# Wifi_Schemati.net
KiCad netlist of a schematic drawn in EAGLE
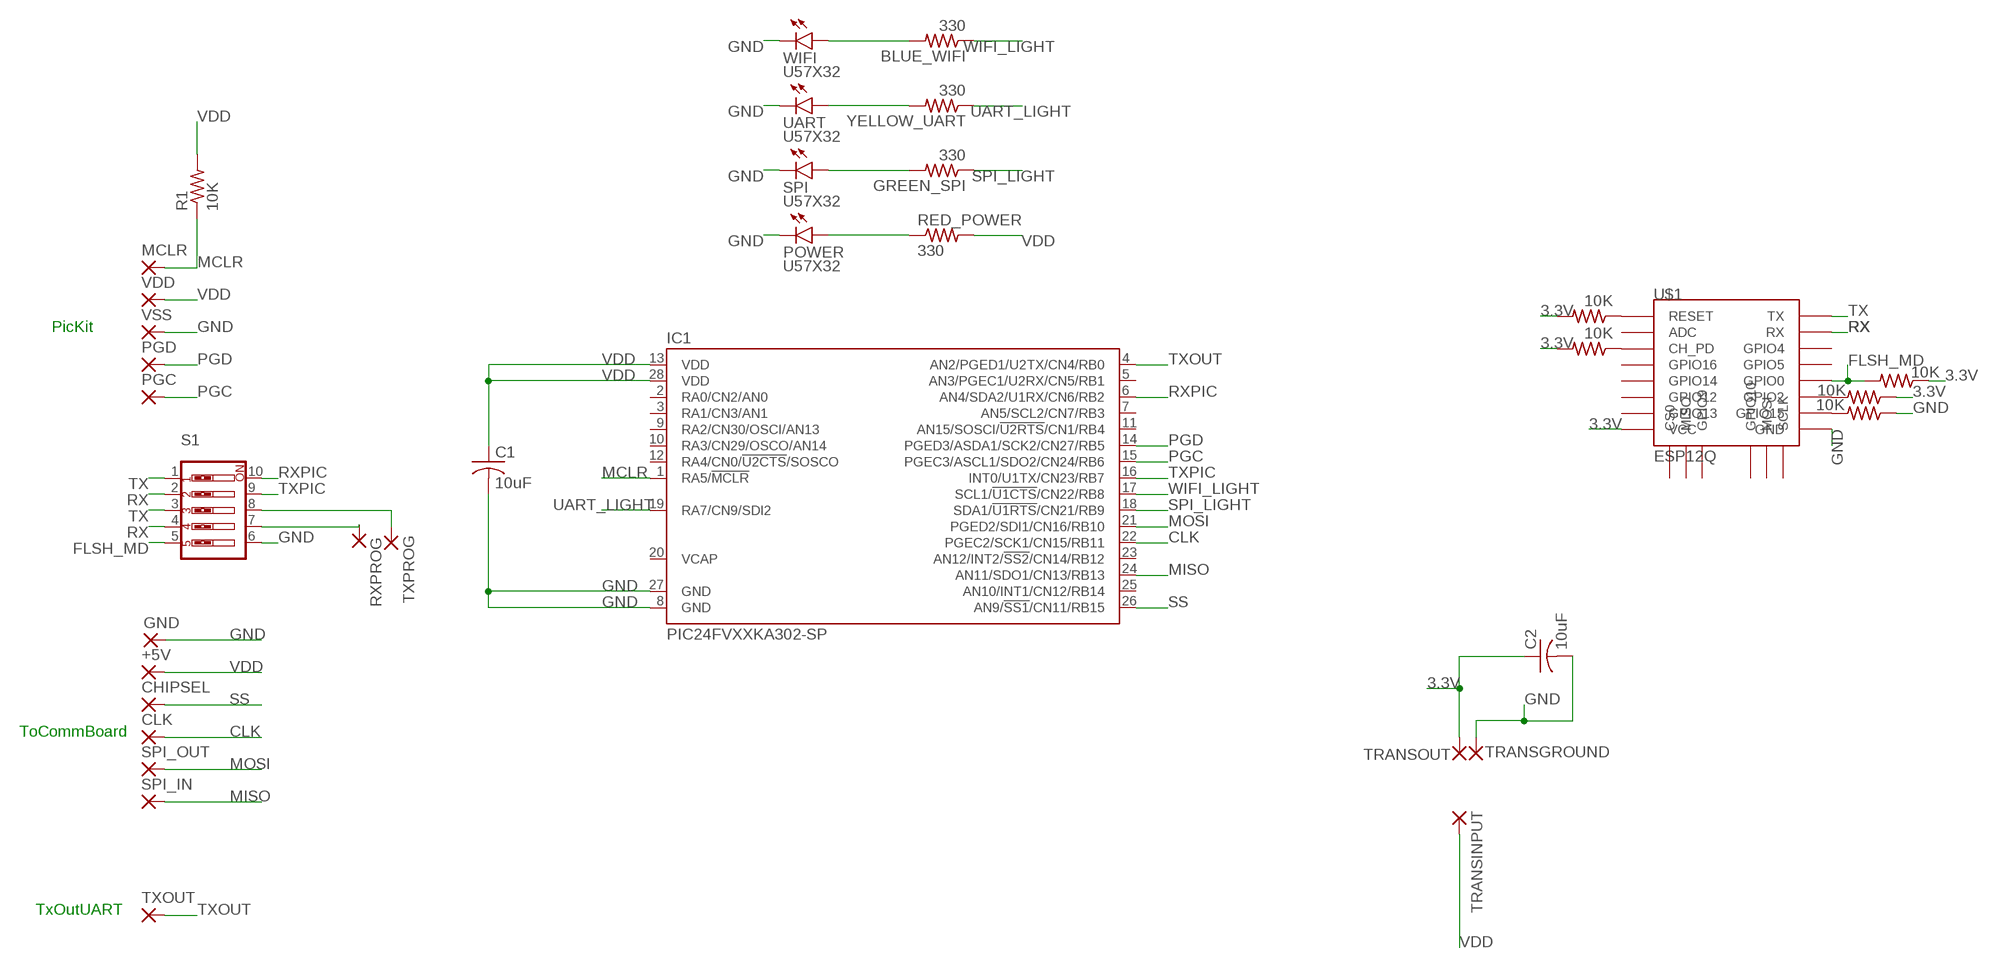
[diagram p0: schematic, sheet 1]

(export (version "E")
  (design (tool "Eeschema 10.0.6"))
  (components
    (comp (ref "+5V")
      (value "1,6/0,8")
      (footprint "eagle-import:1,6_0,8")
      (libsource (lib "eagle-import") (part "1,6/0,8"))
    )
    (comp (ref "BLUE_WIFI")
      (value "330")
      (footprint "eagle-import:0207_7")
      (libsource (lib "eagle-import") (part "R-US_0207/7"))
    )
    (comp (ref "C1")
      (value "10uF")
      (footprint "eagle-import:C025-025X050")
      (libsource (lib "eagle-import") (part "C-US025-025X050"))
    )
    (comp (ref "C2")
      (value "10uF")
      (footprint "eagle-import:C025-025X050")
      (libsource (lib "eagle-import") (part "C-US025-025X050"))
    )
    (comp (ref "CHIPSEL")
      (value "1,6/0,8")
      (footprint "eagle-import:1,6_0,8")
      (libsource (lib "eagle-import") (part "1,6/0,8"))
    )
    (comp (ref "CLK")
      (value "1,6/0,8")
      (footprint "eagle-import:1,6_0,8")
      (libsource (lib "eagle-import") (part "1,6/0,8"))
    )
    (comp (ref "GND")
      (value "1,6/0,8")
      (footprint "eagle-import:1,6_0,8")
      (libsource (lib "eagle-import") (part "1,6/0,8"))
    )
    (comp (ref "GREEN_SPI")
      (value "330")
      (footprint "eagle-import:0207_7")
      (libsource (lib "eagle-import") (part "R-US_0207/7"))
    )
    (comp (ref "IC1")
      (value "PIC24FVXXKA302-SP")
      (footprint "eagle-import:DIL28-3")
      (libsource (lib "eagle-import") (part "PIC24FVXXKA302-SP"))
    )
    (comp (ref "MCLR")
      (value "1,6/0,8")
      (footprint "eagle-import:1,6_0,8")
      (libsource (lib "eagle-import") (part "1,6/0,8"))
    )
    (comp (ref "PGC")
      (value "1,6/0,8")
      (footprint "eagle-import:1,6_0,8")
      (libsource (lib "eagle-import") (part "1,6/0,8"))
    )
    (comp (ref "PGD")
      (value "1,6/0,8")
      (footprint "eagle-import:1,6_0,8")
      (libsource (lib "eagle-import") (part "1,6/0,8"))
    )
    (comp (ref "POWER")
      (value "U57X32")
      (footprint "eagle-import:U57X32")
      (libsource (lib "eagle-import") (part "U57X32"))
    )
    (comp (ref "R1")
      (value "10K")
      (footprint "eagle-import:0207_7")
      (libsource (lib "eagle-import") (part "R-US_0207/7"))
    )
    (comp (ref "R2")
      (value "10K")
      (footprint "eagle-import:0207_7")
      (libsource (lib "eagle-import") (part "R-US_0207/7"))
    )
    (comp (ref "R3")
      (value "10K")
      (footprint "eagle-import:0207_7")
      (libsource (lib "eagle-import") (part "R-US_0207/7"))
    )
    (comp (ref "R4")
      (value "10K")
      (footprint "eagle-import:0207_7")
      (libsource (lib "eagle-import") (part "R-US_0207/7"))
    )
    (comp (ref "R5")
      (value "10K")
      (footprint "eagle-import:0207_7")
      (libsource (lib "eagle-import") (part "R-US_0207/7"))
    )
    (comp (ref "R6")
      (value "10K")
      (footprint "eagle-import:0207_7")
      (libsource (lib "eagle-import") (part "R-US_0207/7"))
    )
    (comp (ref "RED_POWER")
      (value "330")
      (footprint "eagle-import:0207_7")
      (libsource (lib "eagle-import") (part "R-US_0207/7"))
    )
    (comp (ref "RXPROG")
      (value "1,6/0,8")
      (footprint "eagle-import:1,6_0,8")
      (libsource (lib "eagle-import") (part "1,6/0,8"))
    )
    (comp (ref "S1")
      (value "SW_DIP-5")
      (footprint "eagle-import:EDG-05")
      (libsource (lib "eagle-import") (part "SW_DIP-5"))
    )
    (comp (ref "SPI")
      (value "U57X32")
      (footprint "eagle-import:U57X32")
      (libsource (lib "eagle-import") (part "U57X32"))
    )
    (comp (ref "SPI_IN")
      (value "1,6/0,8")
      (footprint "eagle-import:1,6_0,8")
      (libsource (lib "eagle-import") (part "1,6/0,8"))
    )
    (comp (ref "SPI_OUT")
      (value "1,6/0,8")
      (footprint "eagle-import:1,6_0,8")
      (libsource (lib "eagle-import") (part "1,6/0,8"))
    )
    (comp (ref "TRANSGROUND")
      (value "1,6/0,8")
      (footprint "eagle-import:1,6_0,8")
      (libsource (lib "eagle-import") (part "1,6/0,8"))
    )
    (comp (ref "TRANSINPUT")
      (value "1,6/0,8")
      (footprint "eagle-import:1,6_0,8")
      (libsource (lib "eagle-import") (part "1,6/0,8"))
    )
    (comp (ref "TRANSOUT")
      (value "1,6/0,8")
      (footprint "eagle-import:1,6_0,8")
      (libsource (lib "eagle-import") (part "1,6/0,8"))
    )
    (comp (ref "TXOUT")
      (value "1,6/0,8")
      (footprint "eagle-import:1,6_0,8")
      (libsource (lib "eagle-import") (part "1,6/0,8"))
    )
    (comp (ref "TXPROG")
      (value "1,6/0,8")
      (footprint "eagle-import:1,6_0,8")
      (libsource (lib "eagle-import") (part "1,6/0,8"))
    )
    (comp (ref "U$1")
      (value "ESP12Q")
      (footprint "eagle-import:ESP12Q")
      (fields (field (name "SPICEPREFIX") "X"))
      (libsource (lib "eagle-import") (part "ESP12Q"))
    )
    (comp (ref "UART")
      (value "U57X32")
      (footprint "eagle-import:U57X32")
      (libsource (lib "eagle-import") (part "U57X32"))
    )
    (comp (ref "VDD")
      (value "1,6/0,8")
      (footprint "eagle-import:1,6_0,8")
      (libsource (lib "eagle-import") (part "1,6/0,8"))
    )
    (comp (ref "VSS")
      (value "1,6/0,8")
      (footprint "eagle-import:1,6_0,8")
      (libsource (lib "eagle-import") (part "1,6/0,8"))
    )
    (comp (ref "WIFI")
      (value "U57X32")
      (footprint "eagle-import:U57X32")
      (libsource (lib "eagle-import") (part "U57X32"))
    )
    (comp (ref "YELLOW_UART")
      (value "330")
      (footprint "eagle-import:0207_7")
      (libsource (lib "eagle-import") (part "R-US_0207/7"))
    )
  )
  (nets
    (net (code "1") (name "/3.3V") (class "Default")
      (node (ref "C2") (pin "1") (pinfunction "1_1") (pintype "passive"))
      (node (ref "R3") (pin "1") (pinfunction "1_1") (pintype "passive"))
      (node (ref "R4") (pin "1") (pinfunction "1_1") (pintype "passive"))
      (node (ref "R5") (pin "2") (pinfunction "2_2") (pintype "passive"))
      (node (ref "R6") (pin "2") (pinfunction "2_2") (pintype "passive"))
      (node (ref "TRANSOUT") (pin "1") (pinfunction "P_1") (pintype "passive"))
      (node (ref "U$1") (pin "VCC") (pinfunction "VCC_VCC") (pintype "bidirectional"))
    )
    (net (code "2") (name "/CLK") (class "Default")
      (node (ref "CLK") (pin "1") (pinfunction "P_1") (pintype "passive"))
      (node (ref "IC1") (pin "22") (pinfunction "PGEC2/SCK1/CN15/RB11_22") (pintype "bidirectional"))
    )
    (net (code "3") (name "/FLSH_MD") (class "Default")
      (node (ref "R4") (pin "2") (pinfunction "2_2") (pintype "passive"))
      (node (ref "S1") (pin "5") (pinfunction "5_5") (pintype "passive"))
      (node (ref "U$1") (pin "GPIO0") (pinfunction "GPIO0_GPIO0") (pintype "bidirectional"))
    )
    (net (code "4") (name "/GND") (class "Default")
      (node (ref "C1") (pin "2") (pinfunction "2_2") (pintype "passive"))
      (node (ref "C2") (pin "2") (pinfunction "2_2") (pintype "passive"))
      (node (ref "GND") (pin "1") (pinfunction "P_1") (pintype "passive"))
      (node (ref "IC1") (pin "27") (pinfunction "GND_27") (pintype "power_in"))
      (node (ref "IC1") (pin "8") (pinfunction "GND_8") (pintype "power_in"))
      (node (ref "POWER") (pin "K") (pinfunction "C_K") (pintype "passive"))
      (node (ref "R2") (pin "1") (pinfunction "1_1") (pintype "passive"))
      (node (ref "S1") (pin "6") (pinfunction "6_6") (pintype "passive"))
      (node (ref "SPI") (pin "K") (pinfunction "C_K") (pintype "passive"))
      (node (ref "TRANSGROUND") (pin "1") (pinfunction "P_1") (pintype "passive"))
      (node (ref "U$1") (pin "GND") (pinfunction "GND_GND") (pintype "bidirectional"))
      (node (ref "UART") (pin "K") (pinfunction "C_K") (pintype "passive"))
      (node (ref "VSS") (pin "1") (pinfunction "P_1") (pintype "passive"))
      (node (ref "WIFI") (pin "K") (pinfunction "C_K") (pintype "passive"))
    )
    (net (code "5") (name "/MCLR") (class "Default")
      (node (ref "IC1") (pin "1") (pinfunction "RA5/~{MCLR}_1") (pintype "bidirectional"))
      (node (ref "MCLR") (pin "1") (pinfunction "P_1") (pintype "passive"))
      (node (ref "R1") (pin "1") (pinfunction "1_1") (pintype "passive"))
    )
    (net (code "6") (name "/MISO") (class "Default")
      (node (ref "IC1") (pin "24") (pinfunction "AN11/SDO1/CN13/RB13_24") (pintype "bidirectional"))
      (node (ref "SPI_IN") (pin "1") (pinfunction "P_1") (pintype "passive"))
    )
    (net (code "7") (name "/MOSI") (class "Default")
      (node (ref "IC1") (pin "21") (pinfunction "PGED2/SDI1/CN16/RB10_21") (pintype "bidirectional"))
      (node (ref "SPI_OUT") (pin "1") (pinfunction "P_1") (pintype "passive"))
    )
    (net (code "8") (name "/PGC") (class "Default")
      (node (ref "IC1") (pin "15") (pinfunction "PGEC3/ASCL1/SDO2/CN24/RB6_15") (pintype "bidirectional"))
      (node (ref "PGC") (pin "1") (pinfunction "P_1") (pintype "passive"))
    )
    (net (code "9") (name "/PGD") (class "Default")
      (node (ref "IC1") (pin "14") (pinfunction "PGED3/ASDA1/SCK2/CN27/RB5_14") (pintype "bidirectional"))
      (node (ref "PGD") (pin "1") (pinfunction "P_1") (pintype "passive"))
    )
    (net (code "10") (name "/RX") (class "Default")
      (node (ref "S1") (pin "2") (pinfunction "2_2") (pintype "passive"))
      (node (ref "S1") (pin "4") (pinfunction "4_4") (pintype "passive"))
      (node (ref "U$1") (pin "RX") (pinfunction "RX_RX") (pintype "bidirectional"))
    )
    (net (code "11") (name "/RXPIC") (class "Default")
      (node (ref "IC1") (pin "6") (pinfunction "AN4/SDA2/U1RX/CN6/RB2_6") (pintype "bidirectional"))
      (node (ref "S1") (pin "10") (pinfunction "10_10") (pintype "passive"))
    )
    (net (code "12") (name "/SPI_LIGHT") (class "Default")
      (node (ref "GREEN_SPI") (pin "1") (pinfunction "1_1") (pintype "passive"))
      (node (ref "IC1") (pin "18") (pinfunction "SDA1/~{U1RTS}/CN21/RB9_18") (pintype "bidirectional"))
    )
    (net (code "13") (name "/SS") (class "Default")
      (node (ref "CHIPSEL") (pin "1") (pinfunction "P_1") (pintype "passive"))
      (node (ref "IC1") (pin "26") (pinfunction "AN9/~{SS1}/CN11/RB15_26") (pintype "bidirectional"))
    )
    (net (code "14") (name "/TX") (class "Default")
      (node (ref "S1") (pin "1") (pinfunction "1_1") (pintype "passive"))
      (node (ref "S1") (pin "3") (pinfunction "3_3") (pintype "passive"))
      (node (ref "U$1") (pin "TX") (pinfunction "TX_TX") (pintype "bidirectional"))
    )
    (net (code "15") (name "/TXOUT") (class "Default")
      (node (ref "IC1") (pin "4") (pinfunction "AN2/PGED1/U2TX/CN4/RB0_4") (pintype "bidirectional"))
      (node (ref "TXOUT") (pin "1") (pinfunction "P_1") (pintype "passive"))
    )
    (net (code "16") (name "/TXPIC") (class "Default")
      (node (ref "IC1") (pin "16") (pinfunction "INT0/U1TX/CN23/RB7_16") (pintype "bidirectional"))
      (node (ref "S1") (pin "9") (pinfunction "9_9") (pintype "passive"))
    )
    (net (code "17") (name "/UART_LIGHT") (class "Default")
      (node (ref "IC1") (pin "19") (pinfunction "RA7/CN9/SDI2_19") (pintype "bidirectional"))
      (node (ref "YELLOW_UART") (pin "1") (pinfunction "1_1") (pintype "passive"))
    )
    (net (code "18") (name "/VDD") (class "Default")
      (node (ref "+5V") (pin "1") (pinfunction "P_1") (pintype "passive"))
      (node (ref "C1") (pin "1") (pinfunction "1_1") (pintype "passive"))
      (node (ref "IC1") (pin "13") (pinfunction "VDD_13") (pintype "power_in"))
      (node (ref "IC1") (pin "28") (pinfunction "VDD_28") (pintype "power_in"))
      (node (ref "R1") (pin "2") (pinfunction "2_2") (pintype "passive"))
      (node (ref "RED_POWER") (pin "2") (pinfunction "2_2") (pintype "passive"))
      (node (ref "TRANSINPUT") (pin "1") (pinfunction "P_1") (pintype "passive"))
      (node (ref "VDD") (pin "1") (pinfunction "P_1") (pintype "passive"))
    )
    (net (code "19") (name "/WIFI_LIGHT") (class "Default")
      (node (ref "BLUE_WIFI") (pin "1") (pinfunction "1_1") (pintype "passive"))
      (node (ref "IC1") (pin "17") (pinfunction "SCL1/~{U1CTS}/CN22/RB8_17") (pintype "bidirectional"))
    )
    (net (code "20") (name "Net-(BLUE_WIFI-Pad2)") (class "Default")
      (node (ref "BLUE_WIFI") (pin "2") (pinfunction "2_2") (pintype "passive"))
      (node (ref "WIFI") (pin "A") (pinfunction "A_A") (pintype "passive"))
    )
    (net (code "21") (name "Net-(GREEN_SPI-Pad2)") (class "Default")
      (node (ref "GREEN_SPI") (pin "2") (pinfunction "2_2") (pintype "passive"))
      (node (ref "SPI") (pin "A") (pinfunction "A_A") (pintype "passive"))
    )
    (net (code "22") (name "Net-(POWER-PadA)") (class "Default")
      (node (ref "POWER") (pin "A") (pinfunction "A_A") (pintype "passive"))
      (node (ref "RED_POWER") (pin "1") (pinfunction "1_1") (pintype "passive"))
    )
    (net (code "23") (name "Net-(R2-Pad2)") (class "Default")
      (node (ref "R2") (pin "2") (pinfunction "2_2") (pintype "passive"))
      (node (ref "U$1") (pin "GPIO15") (pinfunction "GPIO15_GPIO15") (pintype "bidirectional"))
    )
    (net (code "24") (name "Net-(R3-Pad2)") (class "Default")
      (node (ref "R3") (pin "2") (pinfunction "2_2") (pintype "passive"))
      (node (ref "U$1") (pin "GPIO2") (pinfunction "GPIO2_GPIO2") (pintype "bidirectional"))
    )
    (net (code "25") (name "Net-(R5-Pad1)") (class "Default")
      (node (ref "R5") (pin "1") (pinfunction "1_1") (pintype "passive"))
      (node (ref "U$1") (pin "RESET") (pinfunction "RESET_RESET") (pintype "bidirectional"))
    )
    (net (code "26") (name "Net-(R6-Pad1)") (class "Default")
      (node (ref "R6") (pin "1") (pinfunction "1_1") (pintype "passive"))
      (node (ref "U$1") (pin "CH_PD") (pinfunction "CH_PD_CH_PD") (pintype "bidirectional"))
    )
    (net (code "27") (name "Net-(RXPROG-P)") (class "Default")
      (node (ref "RXPROG") (pin "1") (pinfunction "P_1") (pintype "passive"))
      (node (ref "S1") (pin "7") (pinfunction "7_7") (pintype "passive"))
    )
    (net (code "28") (name "Net-(TXPROG-P)") (class "Default")
      (node (ref "S1") (pin "8") (pinfunction "8_8") (pintype "passive"))
      (node (ref "TXPROG") (pin "1") (pinfunction "P_1") (pintype "passive"))
    )
    (net (code "29") (name "Net-(UART-PadA)") (class "Default")
      (node (ref "UART") (pin "A") (pinfunction "A_A") (pintype "passive"))
      (node (ref "YELLOW_UART") (pin "2") (pinfunction "2_2") (pintype "passive"))
    )
    (net (code "30") (name "unconnected-(IC1-AN3{slash}PGEC1{slash}U2RX{slash}CN5{slash}RB1-Pad5)") (class "Default")
      (node (ref "IC1") (pin "5") (pinfunction "AN3/PGEC1/U2RX/CN5/RB1_5") (pintype "bidirectional"))
    )
    (net (code "31") (name "unconnected-(IC1-AN5{slash}SCL2{slash}CN7{slash}RB3-Pad7)") (class "Default")
      (node (ref "IC1") (pin "7") (pinfunction "AN5/SCL2/CN7/RB3_7") (pintype "bidirectional"))
    )
    (net (code "32") (name "unconnected-(IC1-AN10{slash}INT1{slash}CN12{slash}RB14-Pad25)") (class "Default")
      (node (ref "IC1") (pin "25") (pinfunction "AN10/INT1/CN12/RB14_25") (pintype "bidirectional"))
    )
    (net (code "33") (name "unconnected-(IC1-AN12{slash}INT2{slash}~{SS2}{slash}CN14{slash}RB12-Pad23)") (class "Default")
      (node (ref "IC1") (pin "23") (pinfunction "AN12/INT2/~{SS2}/CN14/RB12_23") (pintype "bidirectional"))
    )
    (net (code "34") (name "unconnected-(IC1-AN15{slash}SOSCI{slash}~{U2RTS}{slash}CN1{slash}RB4-Pad11)") (class "Default")
      (node (ref "IC1") (pin "11") (pinfunction "AN15/SOSCI/~{U2RTS}/CN1/RB4_11") (pintype "bidirectional"))
    )
    (net (code "35") (name "unconnected-(IC1-RA0{slash}CN2{slash}AN0-Pad2)") (class "Default")
      (node (ref "IC1") (pin "2") (pinfunction "RA0/CN2/AN0_2") (pintype "bidirectional"))
    )
    (net (code "36") (name "unconnected-(IC1-RA1{slash}CN3{slash}AN1-Pad3)") (class "Default")
      (node (ref "IC1") (pin "3") (pinfunction "RA1/CN3/AN1_3") (pintype "bidirectional"))
    )
    (net (code "37") (name "unconnected-(IC1-RA2{slash}CN30{slash}OSCI{slash}AN13-Pad9)") (class "Default")
      (node (ref "IC1") (pin "9") (pinfunction "RA2/CN30/OSCI/AN13_9") (pintype "bidirectional"))
    )
    (net (code "38") (name "unconnected-(IC1-RA3{slash}CN29{slash}OSCO{slash}AN14-Pad10)") (class "Default")
      (node (ref "IC1") (pin "10") (pinfunction "RA3/CN29/OSCO/AN14_10") (pintype "bidirectional"))
    )
    (net (code "39") (name "unconnected-(IC1-RA4{slash}CN0{slash}~{U2CTS}{slash}SOSCO-Pad12)") (class "Default")
      (node (ref "IC1") (pin "12") (pinfunction "RA4/CN0/~{U2CTS}/SOSCO_12") (pintype "bidirectional"))
    )
    (net (code "40") (name "unconnected-(IC1-VCAP-Pad20)") (class "Default")
      (node (ref "IC1") (pin "20") (pinfunction "VCAP_20") (pintype "passive"))
    )
    (net (code "41") (name "unconnected-(U$1-PadADC)") (class "Default")
      (node (ref "U$1") (pin "ADC") (pinfunction "ADC_ADC") (pintype "bidirectional"))
    )
    (net (code "42") (name "unconnected-(U$1-PadCS0)") (class "Default")
      (node (ref "U$1") (pin "CS0") (pinfunction "CS0_CS0") (pintype "bidirectional"))
    )
    (net (code "43") (name "unconnected-(U$1-PadGPIO4)") (class "Default")
      (node (ref "U$1") (pin "GPIO4") (pinfunction "GPIO4_GPIO4") (pintype "bidirectional"))
    )
    (net (code "44") (name "unconnected-(U$1-PadGPIO5)") (class "Default")
      (node (ref "U$1") (pin "GPIO5") (pinfunction "GPIO5_GPIO5") (pintype "bidirectional"))
    )
    (net (code "45") (name "unconnected-(U$1-PadGPIO9)") (class "Default")
      (node (ref "U$1") (pin "GPIO9") (pinfunction "GPIO9_GPIO9") (pintype "bidirectional"))
    )
    (net (code "46") (name "unconnected-(U$1-PadGPIO10)") (class "Default")
      (node (ref "U$1") (pin "GPIO10") (pinfunction "GPIO10_GPIO10") (pintype "bidirectional"))
    )
    (net (code "47") (name "unconnected-(U$1-PadGPIO12)") (class "Default")
      (node (ref "U$1") (pin "GPIO12") (pinfunction "GPIO12_GPIO12") (pintype "bidirectional"))
    )
    (net (code "48") (name "unconnected-(U$1-PadGPIO13)") (class "Default")
      (node (ref "U$1") (pin "GPIO13") (pinfunction "GPIO13_GPIO13") (pintype "bidirectional"))
    )
    (net (code "49") (name "unconnected-(U$1-PadGPIO14)") (class "Default")
      (node (ref "U$1") (pin "GPIO14") (pinfunction "GPIO14_GPIO14") (pintype "bidirectional"))
    )
    (net (code "50") (name "unconnected-(U$1-PadGPIO16)") (class "Default")
      (node (ref "U$1") (pin "GPIO16") (pinfunction "GPIO16_GPIO16") (pintype "bidirectional"))
    )
    (net (code "51") (name "unconnected-(U$1-PadMISO)") (class "Default")
      (node (ref "U$1") (pin "MISO") (pinfunction "MISO_MISO") (pintype "bidirectional"))
    )
    (net (code "52") (name "unconnected-(U$1-PadMOSI)") (class "Default")
      (node (ref "U$1") (pin "MOSI") (pinfunction "MOSI_MOSI") (pintype "bidirectional"))
    )
    (net (code "53") (name "unconnected-(U$1-PadSCLK)") (class "Default")
      (node (ref "U$1") (pin "SCLK") (pinfunction "SCLK_SCLK") (pintype "bidirectional"))
    )
  )
)
